# FanMultiplier.net
KiCad netlist of a schematic drawn in EAGLE
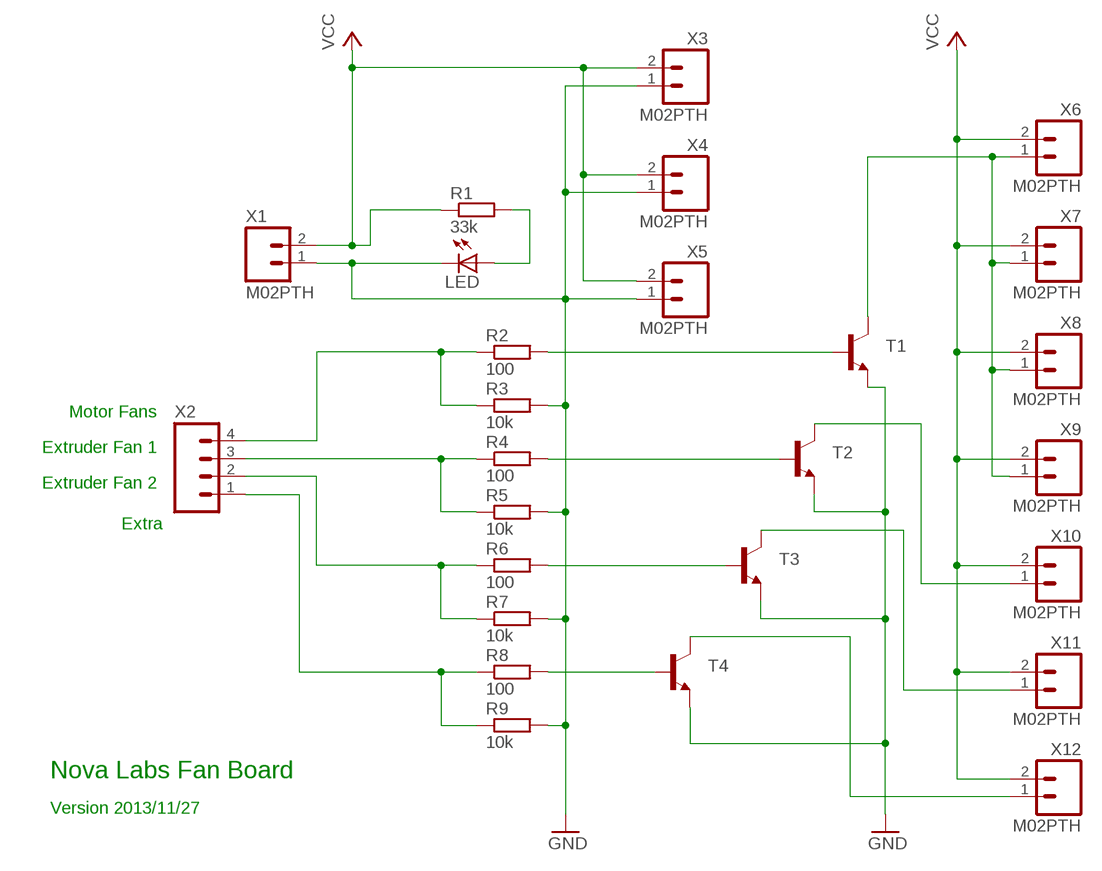
[diagram p0: schematic, sheet 1]

(export (version "E")
  (design (tool "Eeschema 10.0.6"))
  (components
    (comp (ref "LED")
      (value "LED3MM")
      (footprint "eagle-import:LED3MM")
      (libsource (lib "eagle-import") (part "LED3MM"))
    )
    (comp (ref "R1")
      (value "33k")
      (footprint "eagle-import:0207_7")
      (libsource (lib "eagle-import") (part "R-EU_0207/7"))
    )
    (comp (ref "R2")
      (value "100")
      (footprint "eagle-import:0207_7")
      (libsource (lib "eagle-import") (part "R-EU_0207/7"))
    )
    (comp (ref "R3")
      (value "10k")
      (footprint "eagle-import:0207_7")
      (libsource (lib "eagle-import") (part "R-EU_0207/7"))
    )
    (comp (ref "R4")
      (value "100")
      (footprint "eagle-import:0207_7")
      (libsource (lib "eagle-import") (part "R-EU_0207/7"))
    )
    (comp (ref "R5")
      (value "10k")
      (footprint "eagle-import:0207_7")
      (libsource (lib "eagle-import") (part "R-EU_0207/7"))
    )
    (comp (ref "R6")
      (value "100")
      (footprint "eagle-import:0207_7")
      (libsource (lib "eagle-import") (part "R-EU_0207/7"))
    )
    (comp (ref "R7")
      (value "10k")
      (footprint "eagle-import:0207_7")
      (libsource (lib "eagle-import") (part "R-EU_0207/7"))
    )
    (comp (ref "R8")
      (value "100")
      (footprint "eagle-import:0207_7")
      (libsource (lib "eagle-import") (part "R-EU_0207/7"))
    )
    (comp (ref "R9")
      (value "10k")
      (footprint "eagle-import:0207_7")
      (libsource (lib "eagle-import") (part "R-EU_0207/7"))
    )
    (comp (ref "T1")
      (value "TRANSISTOR_NPNTO92")
      (footprint "eagle-import:TO-92")
      (libsource (lib "eagle-import") (part "TRANSISTOR_NPNTO92"))
    )
    (comp (ref "T2")
      (value "TRANSISTOR_NPNTO92")
      (footprint "eagle-import:TO-92")
      (libsource (lib "eagle-import") (part "TRANSISTOR_NPNTO92"))
    )
    (comp (ref "T3")
      (value "TRANSISTOR_NPNTO92")
      (footprint "eagle-import:TO-92")
      (libsource (lib "eagle-import") (part "TRANSISTOR_NPNTO92"))
    )
    (comp (ref "T4")
      (value "TRANSISTOR_NPNTO92")
      (footprint "eagle-import:TO-92")
      (libsource (lib "eagle-import") (part "TRANSISTOR_NPNTO92"))
    )
    (comp (ref "X1")
      (value "M02PTH")
      (footprint "eagle-import:1X02")
      (libsource (lib "eagle-import") (part "M02PTH"))
    )
    (comp (ref "X2")
      (value "M04PTH")
      (footprint "eagle-import:1X04")
      (libsource (lib "eagle-import") (part "M04PTH"))
    )
    (comp (ref "X3")
      (value "M02PTH")
      (footprint "eagle-import:1X02")
      (libsource (lib "eagle-import") (part "M02PTH"))
    )
    (comp (ref "X4")
      (value "M02PTH")
      (footprint "eagle-import:1X02")
      (libsource (lib "eagle-import") (part "M02PTH"))
    )
    (comp (ref "X5")
      (value "M02PTH")
      (footprint "eagle-import:1X02")
      (libsource (lib "eagle-import") (part "M02PTH"))
    )
    (comp (ref "X6")
      (value "M02PTH")
      (footprint "eagle-import:1X02")
      (libsource (lib "eagle-import") (part "M02PTH"))
    )
    (comp (ref "X7")
      (value "M02PTH")
      (footprint "eagle-import:1X02")
      (libsource (lib "eagle-import") (part "M02PTH"))
    )
    (comp (ref "X8")
      (value "M02PTH")
      (footprint "eagle-import:1X02")
      (libsource (lib "eagle-import") (part "M02PTH"))
    )
    (comp (ref "X9")
      (value "M02PTH")
      (footprint "eagle-import:1X02")
      (libsource (lib "eagle-import") (part "M02PTH"))
    )
    (comp (ref "X10")
      (value "M02PTH")
      (footprint "eagle-import:1X02")
      (libsource (lib "eagle-import") (part "M02PTH"))
    )
    (comp (ref "X11")
      (value "M02PTH")
      (footprint "eagle-import:1X02")
      (libsource (lib "eagle-import") (part "M02PTH"))
    )
    (comp (ref "X12")
      (value "M02PTH")
      (footprint "eagle-import:1X02")
      (libsource (lib "eagle-import") (part "M02PTH"))
    )
  )
  (nets
    (net (code "1") (name "GND") (class "Default")
      (node (ref "LED") (pin "K") (pinfunction "C_K") (pintype "passive"))
      (node (ref "R3") (pin "2") (pinfunction "2_2") (pintype "passive"))
      (node (ref "R5") (pin "2") (pinfunction "2_2") (pintype "passive"))
      (node (ref "R7") (pin "2") (pinfunction "2_2") (pintype "passive"))
      (node (ref "R9") (pin "2") (pinfunction "2_2") (pintype "passive"))
      (node (ref "T1") (pin "1") (pinfunction "E_1") (pintype "passive"))
      (node (ref "T2") (pin "1") (pinfunction "E_1") (pintype "passive"))
      (node (ref "T3") (pin "1") (pinfunction "E_1") (pintype "passive"))
      (node (ref "T4") (pin "1") (pinfunction "E_1") (pintype "passive"))
      (node (ref "X1") (pin "1") (pinfunction "1_1") (pintype "passive"))
      (node (ref "X3") (pin "1") (pinfunction "1_1") (pintype "passive"))
      (node (ref "X4") (pin "1") (pinfunction "1_1") (pintype "passive"))
      (node (ref "X5") (pin "1") (pinfunction "1_1") (pintype "passive"))
    )
    (net (code "2") (name "Net-(LED-PadA)") (class "Default")
      (node (ref "LED") (pin "A") (pinfunction "A_A") (pintype "passive"))
      (node (ref "R1") (pin "2") (pinfunction "2_2") (pintype "passive"))
    )
    (net (code "3") (name "Net-(R2-Pad1)") (class "Default")
      (node (ref "R2") (pin "1") (pinfunction "1_1") (pintype "passive"))
      (node (ref "R3") (pin "1") (pinfunction "1_1") (pintype "passive"))
      (node (ref "X2") (pin "4") (pinfunction "4_4") (pintype "passive"))
    )
    (net (code "4") (name "Net-(R4-Pad1)") (class "Default")
      (node (ref "R4") (pin "1") (pinfunction "1_1") (pintype "passive"))
      (node (ref "R5") (pin "1") (pinfunction "1_1") (pintype "passive"))
      (node (ref "X2") (pin "3") (pinfunction "3_3") (pintype "passive"))
    )
    (net (code "5") (name "Net-(R6-Pad1)") (class "Default")
      (node (ref "R6") (pin "1") (pinfunction "1_1") (pintype "passive"))
      (node (ref "R7") (pin "1") (pinfunction "1_1") (pintype "passive"))
      (node (ref "X2") (pin "2") (pinfunction "2_2") (pintype "passive"))
    )
    (net (code "6") (name "Net-(R8-Pad1)") (class "Default")
      (node (ref "R8") (pin "1") (pinfunction "1_1") (pintype "passive"))
      (node (ref "R9") (pin "1") (pinfunction "1_1") (pintype "passive"))
      (node (ref "X2") (pin "1") (pinfunction "1_1") (pintype "passive"))
    )
    (net (code "7") (name "Net-(T1-B)") (class "Default")
      (node (ref "R2") (pin "2") (pinfunction "2_2") (pintype "passive"))
      (node (ref "T1") (pin "2") (pinfunction "B_2") (pintype "passive"))
    )
    (net (code "8") (name "Net-(T1-C)") (class "Default")
      (node (ref "T1") (pin "3") (pinfunction "C_3") (pintype "passive"))
      (node (ref "X6") (pin "1") (pinfunction "1_1") (pintype "passive"))
      (node (ref "X7") (pin "1") (pinfunction "1_1") (pintype "passive"))
      (node (ref "X8") (pin "1") (pinfunction "1_1") (pintype "passive"))
      (node (ref "X9") (pin "1") (pinfunction "1_1") (pintype "passive"))
    )
    (net (code "9") (name "Net-(T2-B)") (class "Default")
      (node (ref "R4") (pin "2") (pinfunction "2_2") (pintype "passive"))
      (node (ref "T2") (pin "2") (pinfunction "B_2") (pintype "passive"))
    )
    (net (code "10") (name "Net-(T2-C)") (class "Default")
      (node (ref "T2") (pin "3") (pinfunction "C_3") (pintype "passive"))
      (node (ref "X10") (pin "1") (pinfunction "1_1") (pintype "passive"))
    )
    (net (code "11") (name "Net-(T3-B)") (class "Default")
      (node (ref "R6") (pin "2") (pinfunction "2_2") (pintype "passive"))
      (node (ref "T3") (pin "2") (pinfunction "B_2") (pintype "passive"))
    )
    (net (code "12") (name "Net-(T3-C)") (class "Default")
      (node (ref "T3") (pin "3") (pinfunction "C_3") (pintype "passive"))
      (node (ref "X11") (pin "1") (pinfunction "1_1") (pintype "passive"))
    )
    (net (code "13") (name "Net-(T4-B)") (class "Default")
      (node (ref "R8") (pin "2") (pinfunction "2_2") (pintype "passive"))
      (node (ref "T4") (pin "2") (pinfunction "B_2") (pintype "passive"))
    )
    (net (code "14") (name "Net-(T4-C)") (class "Default")
      (node (ref "T4") (pin "3") (pinfunction "C_3") (pintype "passive"))
      (node (ref "X12") (pin "1") (pinfunction "1_1") (pintype "passive"))
    )
    (net (code "15") (name "VCC") (class "Default")
      (node (ref "R1") (pin "1") (pinfunction "1_1") (pintype "passive"))
      (node (ref "X1") (pin "2") (pinfunction "2_2") (pintype "passive"))
      (node (ref "X10") (pin "2") (pinfunction "2_2") (pintype "passive"))
      (node (ref "X11") (pin "2") (pinfunction "2_2") (pintype "passive"))
      (node (ref "X12") (pin "2") (pinfunction "2_2") (pintype "passive"))
      (node (ref "X3") (pin "2") (pinfunction "2_2") (pintype "passive"))
      (node (ref "X4") (pin "2") (pinfunction "2_2") (pintype "passive"))
      (node (ref "X5") (pin "2") (pinfunction "2_2") (pintype "passive"))
      (node (ref "X6") (pin "2") (pinfunction "2_2") (pintype "passive"))
      (node (ref "X7") (pin "2") (pinfunction "2_2") (pintype "passive"))
      (node (ref "X8") (pin "2") (pinfunction "2_2") (pintype "passive"))
      (node (ref "X9") (pin "2") (pinfunction "2_2") (pintype "passive"))
    )
  )
)
